# Main.net
KiCad netlist of a schematic drawn in Altium Designer
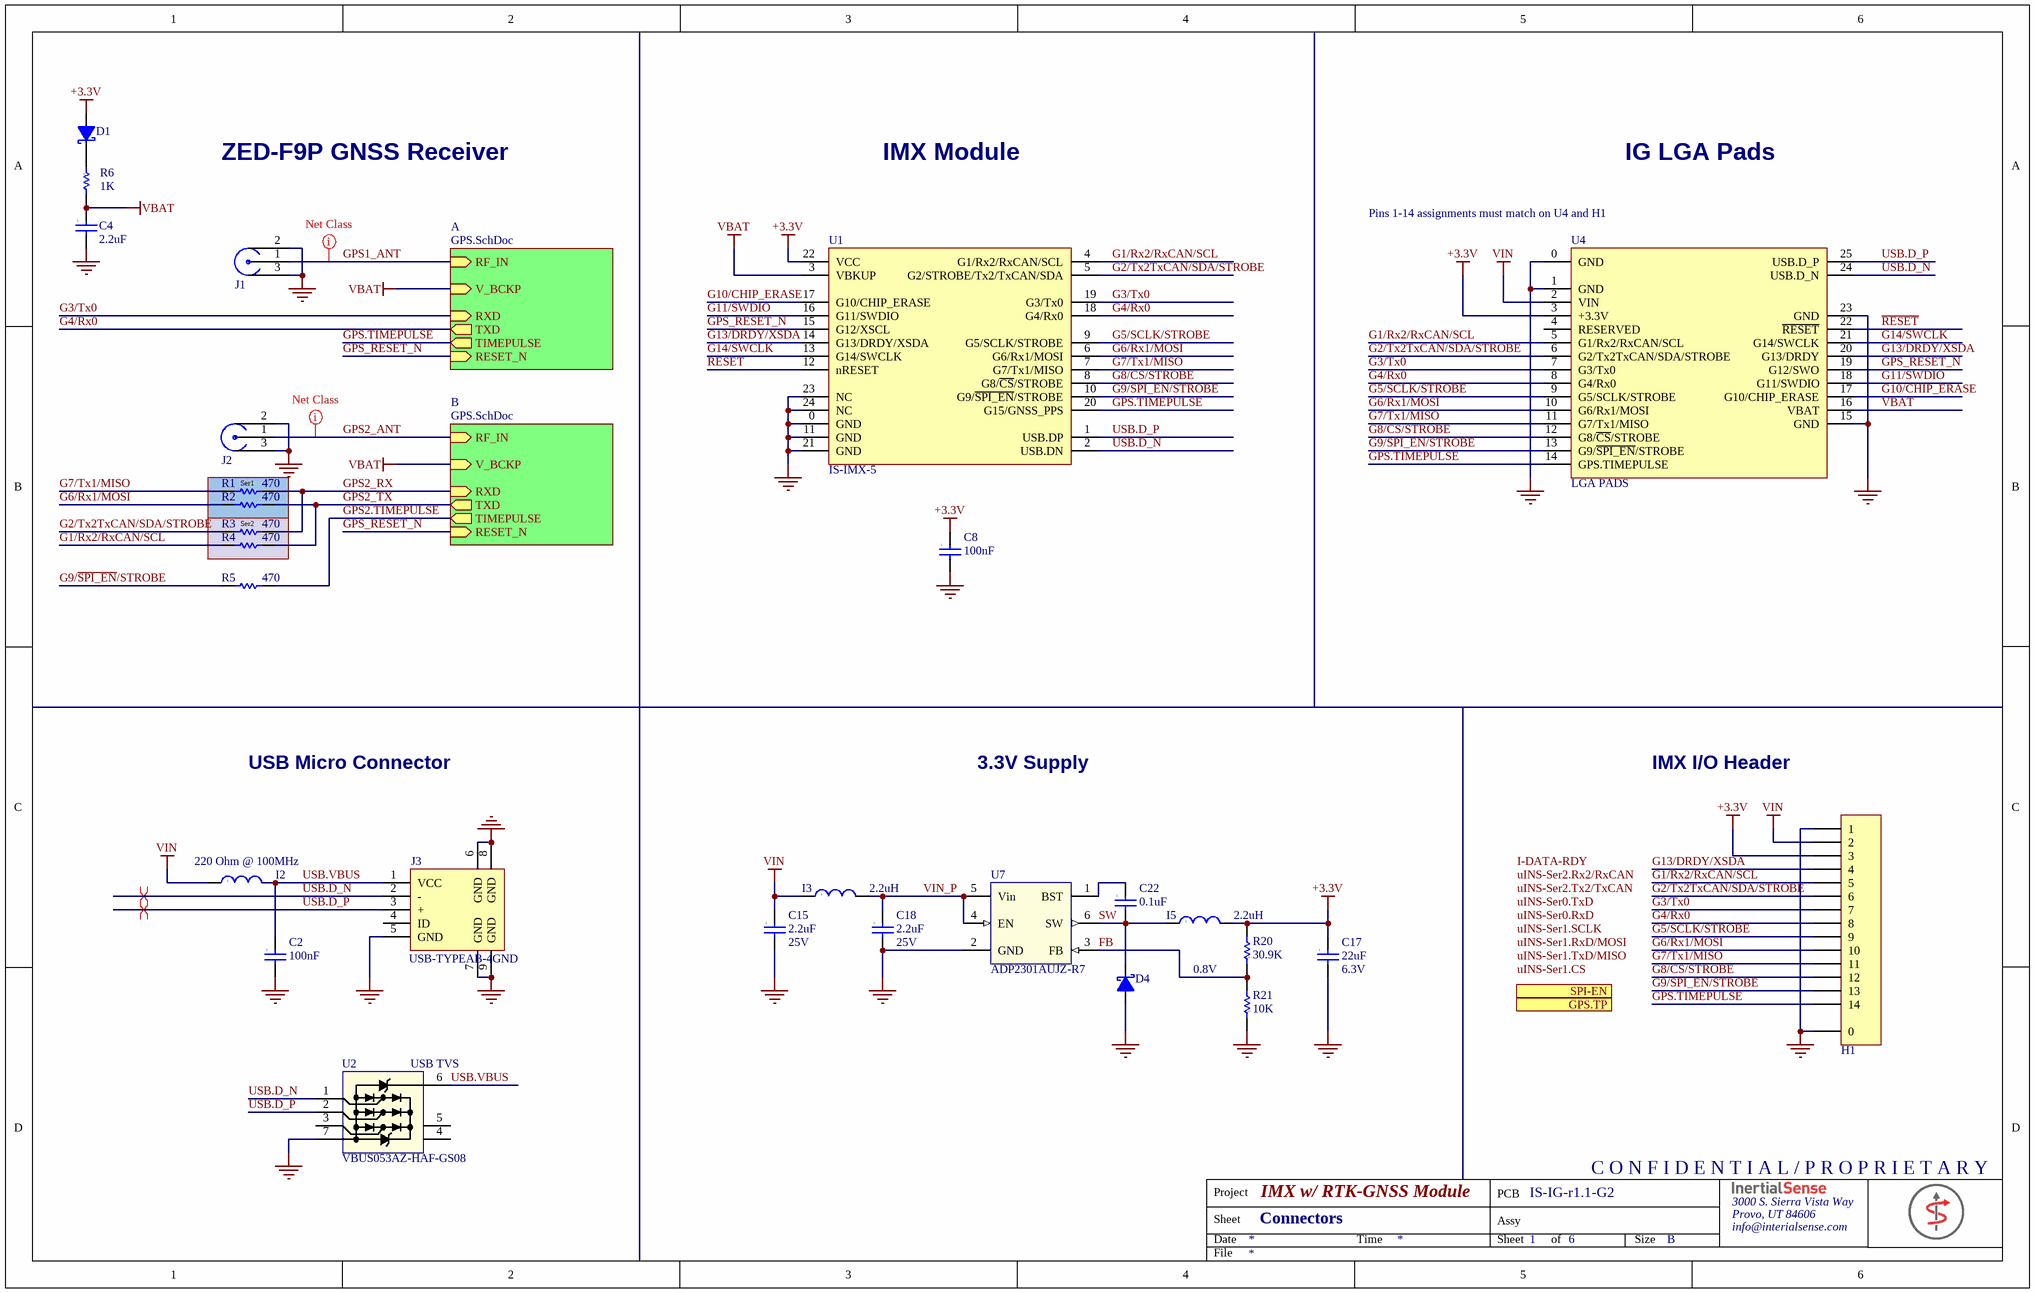
[diagram p0: Main.SchDoc]

(export (version "E")
  (design (tool "Eeschema 10.0.6"))
  (components
    (comp (ref "C2")
      (value "100nF")
      (footprint "0402")
      (description "CAP CER .10UF 50V X7R 10% 0402")
      (fields
        (field (name "MANUFACTURER") "TDK Corporation")
        (field (name "MANUFACTURER PART NUMBER") "C1005X7R1H104K")
        (field (name "PUBLISHER") "Altium Limited")
      )
      (libsource (lib "") (part "Cap_1"))
    )
    (comp (ref "C4")
      (value "2.2uF")
      (footprint "0402")
      (description "0402 2.2 uF 6.3 V ±10% Tolerance X6S Multilayer Ceramic Capacitor")
      (fields
        (field (name "MANUFACTURER") "Murata")
        (field (name "MANUFACTURER PART NUMBER") "GRM155C80J225KE95D")
        (field (name "PUBLISHER") "Altium Limited")
      )
      (libsource (lib "General") (part "Cap"))
    )
    (comp (ref "C8")
      (value "100nF")
      (footprint "0402")
      (description "CAP CER .10UF 50V X7R 10% 0402")
      (fields
        (field (name "MANUFACTURER") "TDK Corporation")
        (field (name "MANUFACTURER PART NUMBER") "C1005X7R1H104K")
        (field (name "PUBLISHER") "Altium Limited")
      )
      (libsource (lib "") (part "Cap_1"))
    )
    (comp (ref "C15")
      (value "2.2uF")
      (footprint "0603")
      (description "CAP CER 2.2UF 25V X6S 0603")
      (fields
        (field (name "MANUFACTURER") "Murata")
        (field (name "MANUFACTURER PART NUMBER") "GRT188C81E225KE13D")
        (field (name "VOLTAGE RATING") "25V")
        (field (name "PUBLISHER") "Altium Limited")
      )
      (libsource (lib "General") (part "Cap"))
    )
    (comp (ref "C17")
      (value "22uF")
      (footprint "0603")
      (description "CAP CER 22UF 6.3V X6S 0603")
      (fields
        (field (name "MANUFACTURER") "Murata")
        (field (name "MANUFACTURER PART NUMBER") "GRM188C80J226ME15D")
        (field (name "VOLTAGE RATING") "6.3V")
        (field (name "PUBLISHER") "Altium Limited")
      )
      (libsource (lib "General") (part "Cap"))
    )
    (comp (ref "C18")
      (value "2.2uF")
      (footprint "0603")
      (description "CAP CER 2.2UF 25V X6S 0603")
      (fields
        (field (name "MANUFACTURER") "Murata")
        (field (name "MANUFACTURER PART NUMBER") "GRT188C81E225KE13D")
        (field (name "VOLTAGE RATING") "25V")
        (field (name "PUBLISHER") "Altium Limited")
      )
      (libsource (lib "General") (part "Cap"))
    )
    (comp (ref "C22")
      (value "0.1uF")
      (footprint "0402")
      (description "CAP CER 0.1UF 50V X7R 0402")
      (fields
        (field (name "MANUFACTURER") "TDK")
        (field (name "MANUFACTURER PART NUMBER") "CGA2B3X7R1H104K050BB")
        (field (name "PUBLISHER") "Altium Limited")
      )
      (libsource (lib "General") (part "Cap"))
    )
    (comp (ref "D1")
      (value "Diode - Schottky")
      (footprint "D0603B")
      (description "DIODE SCHOTTKY 30V 2A 0603")
      (fields
        (field (name "MANUFACTURER") "Vishay")
        (field (name "MANUFACTURER PART NUMBER") "VSKY20301608-G4-08")
      )
      (libsource (lib "General") (part "Diode - Schottky"))
    )
    (comp (ref "D4")
      (value "Diode - Schottky")
      (footprint "D0603B")
      (description "DIODE SCHOTTKY 30V 2A 0603")
      (fields
        (field (name "MANUFACTURER") "Vishay")
        (field (name "MANUFACTURER PART NUMBER") "VSKY20301608-G4-08")
      )
      (libsource (lib "General") (part "Diode - Schottky"))
    )
    (comp (ref "H1")
      (value "Hdr - 14pin - mount")
      (footprint "SM14B-GHS-TB(LF)(SN)")
      (description "Conn Shrouded Header HDR 14 POS 1.25mm Solder ST Top Entry SMD T/R")
      (fields
        (field (name "MANUFACTURER") "JST")
        (field (name "MANUFACTURER PART NUMBER") "SM14B-GHS-TB(LF)(SN)")
      )
      (libsource (lib "Connectors") (part "Hdr - 14pin - mount"))
    )
    (comp (ref "I2")
      (value "220 Ohm @ 100MHz")
      (footprint "I0603")
      (description "FERRITE CHIP 220 OHM 2500MA 0603")
      (fields
        (field (name "MANUFACTURER") "Murata Electronics North America")
        (field (name "MANUFACTURER PART NUMBER") "BLM18SG221TN1D")
      )
      (libsource (lib "") (part "Inductor_1"))
    )
    (comp (ref "I3")
      (value "2.2uH")
      (footprint "0806")
      (description "FIXED IND 2.2UH 1.2A 110 MOHM")
      (fields
        (field (name "MANUFACTURER") "TDK")
        (field (name "MANUFACTURER PART NUMBER") "MLP2016H2R2MT0S1")
      )
      (libsource (lib "General") (part "Inductor"))
    )
    (comp (ref "I5")
      (value "2.2uH")
      (footprint "0806")
      (description "FIXED IND 2.2UH 1.2A 110 MOHM")
      (fields
        (field (name "MANUFACTURER") "TDK")
        (field (name "MANUFACTURER PART NUMBER") "MLP2016H2R2MT0S1")
      )
      (libsource (lib "General") (part "Inductor"))
    )
    (comp (ref "J1")
      (value "RF - GND x 2")
      (footprint "RF UMC SMD")
      (description "CONN UMC RCPT STR 50 OHM SMD")
      (fields
        (field (name "MANUFACTURER") "Emerson Network Power Connectivity Johnson")
        (field (name "MANUFACTURER PART NUMBER") "128-0711-201")
      )
      (libsource (lib "Connectors") (part "RF - GND x 2"))
    )
    (comp (ref "J2")
      (value "RF - GND x 2")
      (footprint "RF UMC SMD")
      (description "CONN UMC RCPT STR 50 OHM SMD")
      (fields
        (field (name "MANUFACTURER") "Emerson Network Power Connectivity Johnson")
        (field (name "MANUFACTURER PART NUMBER") "128-0711-201")
      )
      (libsource (lib "Connectors") (part "RF - GND x 2"))
    )
    (comp (ref "J3")
      (value "USB-TYPEAB-4GND")
      (footprint "USB Micro AB R/A THR")
      (description "CONN USB AB 4POS")
      (fields
        (field (name "MANUFACTURER") "Amphenol FCI")
        (field (name "MANUFACTURER PART NUMBER") "10118194-0001LF")
      )
      (libsource (lib "Connectors") (part "USB-TYPEAB-4GND"))
    )
    (comp (ref "R1")
      (value "470")
      (footprint "R0402")
      (description "RES 470 OHM 1/16W 1% 0402 SMD")
      (fields
        (field (name "MANUFACTURER") "Vishay Dale")
        (field (name "MANUFACTURER PART NUMBER") "CRCW0402470RFKED")
      )
      (libsource (lib "") (part "Res_1"))
    )
    (comp (ref "R2")
      (value "470")
      (footprint "R0402")
      (description "RES 470 OHM 1/16W 1% 0402 SMD")
      (fields
        (field (name "MANUFACTURER") "Vishay Dale")
        (field (name "MANUFACTURER PART NUMBER") "CRCW0402470RFKED")
      )
      (libsource (lib "") (part "Res_1"))
    )
    (comp (ref "R3")
      (value "470")
      (footprint "R0402")
      (description "RES 470 OHM 1/16W 1% 0402 SMD")
      (fields
        (field (name "MANUFACTURER") "Vishay Dale")
        (field (name "MANUFACTURER PART NUMBER") "CRCW0402470RFKED")
      )
      (libsource (lib "") (part "Res_1"))
    )
    (comp (ref "R4")
      (value "470")
      (footprint "R0402")
      (description "RES 470 OHM 1/16W 1% 0402 SMD")
      (fields
        (field (name "MANUFACTURER") "Vishay Dale")
        (field (name "MANUFACTURER PART NUMBER") "CRCW0402470RFKED")
      )
      (libsource (lib "") (part "Res_1"))
    )
    (comp (ref "R5")
      (value "470")
      (footprint "R0402")
      (description "RES 470 OHM 1/16W 1% 0402 SMD")
      (fields
        (field (name "MANUFACTURER") "Vishay Dale")
        (field (name "MANUFACTURER PART NUMBER") "CRCW0402470RFKED")
      )
      (libsource (lib "") (part "Res_1"))
    )
    (comp (ref "R6")
      (value "1K")
      (footprint "R0402")
      (description "1 kOhms ±1% 0.063W, 1/16W Chip Resistor 0402 (1005 Metric) Moisture Resistant Thick Film")
      (fields
        (field (name "MANUFACTURER") "Yageo")
        (field (name "MANUFACTURER PART NUMBER") "RC0402FR-071KL")
      )
      (libsource (lib "") (part "Res_2"))
    )
    (comp (ref "R20")
      (value "30.9K")
      (footprint "R0402")
      (description "RES TF 30.9K OHM 1% 1/16W 0402")
      (fields
        (field (name "MANUFACTURER") "Stackpole Electronics Inc")
        (field (name "MANUFACTURER PART NUMBER") "RMCF0402FT30K9")
      )
      (libsource (lib "General") (part "Res"))
    )
    (comp (ref "R21")
      (value "10K")
      (footprint "R0402")
      (description "RES 10.0K OHM 1/16W 1% 0402 SMD")
      (fields
        (field (name "MANUFACTURER") "Yageo")
        (field (name "MANUFACTURER PART NUMBER") "RC0402FR-0710KL")
      )
      (libsource (lib "General") (part "Res"))
    )
    (comp (ref "U1")
      (value "IMX")
      (footprint "IS-IMX-5.0")
      (description "Inertial Sense IMX")
      (fields
        (field (name "MANUFACTURER") "Inertial Sense")
        (field (name "MANUFACTURER PART NUMBER") "IS-IMX-5")
      )
      (libsource (lib "IS-IMX-5") (part "IS-IMX-5.0"))
    )
    (comp (ref "U2")
      (value "VBUS053")
      (footprint "QFN50P160X160X60-6N")
      (description "ESD SUPPRESS 5.5V 36W 3-Line USB")
      (fields
        (field (name "MANUFACTURER") "Vishay Semiconductors")
        (field (name "MANUFACTURER PART NUMBER") "VBUS053AZ-HAF-GS08")
      )
      (libsource (lib "ICs") (part "VBUS053"))
    )
    (comp (ref "U4")
      (value "LGA PADS")
      (footprint "IG-1.1-G1_LGA")
      (description "IMX multi-frequency RTK-GNSS Module")
      (libsource (lib "Sensors") (part "IG_1.1_LGA"))
    )
    (comp (ref "U7")
      (value "ADP2301")
      (footprint "MO-178-AB")
      (description "IC BUCK ADJ 1.2A 6TSOT")
      (fields
        (field (name "MANUFACTURER") "Analog Devices Inc")
        (field (name "MANUFACTURER PART NUMBER") "ADP2301AUJZ-R7")
      )
      (libsource (lib "ICs") (part "ADP2301"))
    )
  )
  (nets
    (net (code "1") (name "+3.3V") (class "Default")
      (node (ref "C17") (pin "1") (pinfunction "1_1") (pintype "passive"))
      (node (ref "C8") (pin "1") (pinfunction "1_1") (pintype "passive"))
      (node (ref "D1") (pin "A") (pinfunction "A_A") (pintype "passive"))
      (node (ref "H1") (pin "3") (pinfunction "3_3") (pintype "passive"))
      (node (ref "I5") (pin "2") (pinfunction "2_2") (pintype "passive"))
      (node (ref "R20") (pin "2") (pinfunction "2_2") (pintype "passive"))
      (node (ref "U1") (pin "22") (pinfunction "VCC_22") (pintype "power_in"))
      (node (ref "U4") (pin "3") (pinfunction "+3.3V_3") (pintype "passive"))
    )
    (net (code "2") (name "/FB") (class "Default")
      (node (ref "R20") (pin "1") (pinfunction "1_1") (pintype "passive"))
      (node (ref "R21") (pin "2") (pinfunction "2_2") (pintype "passive"))
      (node (ref "U7") (pin "3") (pinfunction "FB_3") (pintype "input"))
    )
    (net (code "3") (name "/G1{slash}Rx2{slash}RxCAN{slash}SCL") (class "Default")
      (node (ref "H1") (pin "5") (pinfunction "5_5") (pintype "passive"))
      (node (ref "R4") (pin "1") (pinfunction "1_1") (pintype "passive"))
      (node (ref "U1") (pin "4") (pinfunction "G1/Rx2/RxCAN/SCL_4") (pintype "passive"))
      (node (ref "U4") (pin "5") (pinfunction "G1/Rx2/RxCAN/SCL_5") (pintype "passive"))
    )
    (net (code "4") (name "/G2{slash}Tx2TxCAN{slash}SDA{slash}STROBE") (class "Default")
      (node (ref "H1") (pin "6") (pinfunction "6_6") (pintype "passive"))
      (node (ref "R3") (pin "1") (pinfunction "1_1") (pintype "passive"))
      (node (ref "U1") (pin "5") (pinfunction "G2/STROBE/Tx2/TxCAN/SDA_5") (pintype "passive"))
      (node (ref "U4") (pin "6") (pinfunction "G2/Tx2TxCAN/SDA/STROBE_6") (pintype "passive"))
    )
    (net (code "5") (name "/G3{slash}Tx0") (class "Default")
      (node (ref "H1") (pin "7") (pinfunction "7_7") (pintype "passive"))
      (node (ref "U1") (pin "19") (pinfunction "G3/Tx0_19") (pintype "passive"))
      (node (ref "U4") (pin "7") (pinfunction "G3/Tx0_7") (pintype "passive"))
    )
    (net (code "6") (name "/G4{slash}Rx0") (class "Default")
      (node (ref "H1") (pin "8") (pinfunction "8_8") (pintype "passive"))
      (node (ref "U1") (pin "18") (pinfunction "G4/Rx0_18") (pintype "passive"))
      (node (ref "U4") (pin "8") (pinfunction "G4/Rx0_8") (pintype "passive"))
    )
    (net (code "7") (name "/G5{slash}SCLK{slash}STROBE") (class "Default")
      (node (ref "H1") (pin "9") (pinfunction "9_9") (pintype "passive"))
      (node (ref "U1") (pin "9") (pinfunction "G5/SCLK/STROBE_9") (pintype "passive"))
      (node (ref "U4") (pin "9") (pinfunction "G5/SCLK/STROBE_9") (pintype "passive"))
    )
    (net (code "8") (name "/G6{slash}Rx1{slash}MOSI") (class "Default")
      (node (ref "H1") (pin "10") (pinfunction "10_10") (pintype "passive"))
      (node (ref "R2") (pin "1") (pinfunction "1_1") (pintype "passive"))
      (node (ref "U1") (pin "6") (pinfunction "G6/Rx1/MOSI_6") (pintype "passive"))
      (node (ref "U4") (pin "10") (pinfunction "G6/Rx1/MOSI_10") (pintype "passive"))
    )
    (net (code "9") (name "/G7{slash}Tx1{slash}MISO") (class "Default")
      (node (ref "H1") (pin "11") (pinfunction "11_11") (pintype "passive"))
      (node (ref "R1") (pin "1") (pinfunction "1_1") (pintype "passive"))
      (node (ref "U1") (pin "7") (pinfunction "G7/Tx1/MISO_7") (pintype "passive"))
      (node (ref "U4") (pin "11") (pinfunction "G7/Tx1/MISO_11") (pintype "passive"))
    )
    (net (code "10") (name "/G8{slash}~{CS}{slash}STROBE") (class "Default")
      (node (ref "H1") (pin "12") (pinfunction "12_12") (pintype "passive"))
      (node (ref "U1") (pin "8") (pinfunction "G8/~{CS}/STROBE_8") (pintype "passive"))
      (node (ref "U4") (pin "12") (pinfunction "G8/~{CS}/STROBE_12") (pintype "passive"))
    )
    (net (code "11") (name "/G9{slash}~{SPI_EN}{slash}STROBE") (class "Default")
      (node (ref "H1") (pin "13") (pinfunction "13_13") (pintype "passive"))
      (node (ref "R5") (pin "1") (pinfunction "1_1") (pintype "passive"))
      (node (ref "U1") (pin "10") (pinfunction "G9/~{SPI_EN}/STROBE_10") (pintype "passive"))
      (node (ref "U4") (pin "13") (pinfunction "G9/~{SPI_EN}/STROBE_13") (pintype "passive"))
    )
    (net (code "12") (name "/G10{slash}CHIP_ERASE") (class "Default")
      (node (ref "U1") (pin "17") (pinfunction "G10/CHIP_ERASE_17") (pintype "passive"))
      (node (ref "U4") (pin "17") (pinfunction "G10/CHIP_ERASE_17") (pintype "passive"))
    )
    (net (code "13") (name "/G11{slash}SWDIO") (class "Default")
      (node (ref "U1") (pin "16") (pinfunction "G11/SWDIO_16") (pintype "passive"))
      (node (ref "U4") (pin "18") (pinfunction "G11/SWDIO_18") (pintype "passive"))
    )
    (net (code "14") (name "/G13{slash}DRDY{slash}XSDA") (class "Default")
      (node (ref "H1") (pin "4") (pinfunction "4_4") (pintype "passive"))
      (node (ref "U1") (pin "14") (pinfunction "G13/DRDY/XSDA_14") (pintype "passive"))
      (node (ref "U4") (pin "20") (pinfunction "G13/DRDY_20") (pintype "passive"))
    )
    (net (code "15") (name "/G14{slash}SWCLK") (class "Default")
      (node (ref "U1") (pin "13") (pinfunction "G14/SWCLK_13") (pintype "passive"))
      (node (ref "U4") (pin "21") (pinfunction "G14/SWCLK_21") (pintype "passive"))
    )
    (net (code "16") (name "/GPS.TIMEPULSE") (class "Default")
      (node (ref "H1") (pin "14") (pinfunction "14_14") (pintype "passive"))
      (node (ref "U1") (pin "20") (pinfunction "G15/GNSS_PPS_20") (pintype "passive"))
      (node (ref "U4") (pin "14") (pinfunction "GPS.TIMEPULSE_14") (pintype "passive"))
    )
    (net (code "18") (name "/GPS1_ANT") (class "Default")
      (node (ref "J1") (pin "1") (pinfunction "1_1") (pintype "passive"))
    )
    (net (code "19") (name "/GPS2.TIMEPULSE") (class "Default")
      (node (ref "R5") (pin "2") (pinfunction "2_2") (pintype "passive"))
    )
    (net (code "20") (name "/GPS2_ANT") (class "Default")
      (node (ref "J2") (pin "1") (pinfunction "1_1") (pintype "passive"))
    )
    (net (code "21") (name "/GPS2_RX") (class "Default")
      (node (ref "R1") (pin "2") (pinfunction "2_2") (pintype "passive"))
      (node (ref "R3") (pin "2") (pinfunction "2_2") (pintype "passive"))
    )
    (net (code "22") (name "/GPS2_TX") (class "Default")
      (node (ref "R2") (pin "2") (pinfunction "2_2") (pintype "passive"))
      (node (ref "R4") (pin "2") (pinfunction "2_2") (pintype "passive"))
    )
    (net (code "23") (name "/GPS_RESET_N") (class "Default")
      (node (ref "U1") (pin "15") (pinfunction "G12/XSCL_15") (pintype "passive"))
      (node (ref "U4") (pin "19") (pinfunction "G12/SWO_19") (pintype "passive"))
    )
    (net (code "25") (name "/RESET") (class "Default")
      (node (ref "U1") (pin "12") (pinfunction "nRESET_12") (pintype "passive"))
      (node (ref "U4") (pin "22") (pinfunction "~{RESET}_22") (pintype "passive"))
    )
    (net (code "27") (name "/SW") (class "Default")
      (node (ref "C22") (pin "2") (pinfunction "2_2") (pintype "passive"))
      (node (ref "D4") (pin "C") (pinfunction "C_C") (pintype "passive"))
      (node (ref "I5") (pin "1") (pinfunction "1_1") (pintype "passive"))
      (node (ref "U7") (pin "6") (pinfunction "SW_6") (pintype "output"))
    )
    (net (code "28") (name "/USB.D_N") (class "Default")
      (node (ref "J3") (pin "2") (pinfunction "-_2") (pintype "passive"))
      (node (ref "U1") (pin "2") (pinfunction "USB.DN_2") (pintype "passive"))
      (node (ref "U2") (pin "1") (pintype "passive"))
      (node (ref "U4") (pin "24") (pinfunction "USB.D_N_24") (pintype "passive"))
    )
    (net (code "29") (name "/USB.D_P") (class "Default")
      (node (ref "J3") (pin "3") (pinfunction "+_3") (pintype "passive"))
      (node (ref "U1") (pin "1") (pinfunction "USB.DP_1") (pintype "passive"))
      (node (ref "U2") (pin "2") (pintype "passive"))
      (node (ref "U4") (pin "25") (pinfunction "USB.D_P_25") (pintype "passive"))
    )
    (net (code "30") (name "/USB.VBUS") (class "Default")
      (node (ref "C2") (pin "1") (pinfunction "1_1") (pintype "passive"))
      (node (ref "I2") (pin "2") (pinfunction "2_2") (pintype "passive"))
      (node (ref "J3") (pin "1") (pinfunction "VCC_1") (pintype "passive"))
      (node (ref "U2") (pin "6") (pintype "passive"))
    )
    (net (code "31") (name "/VIN_P") (class "Default")
      (node (ref "C18") (pin "1") (pinfunction "1_1") (pintype "passive"))
      (node (ref "I3") (pin "2") (pinfunction "2_2") (pintype "passive"))
      (node (ref "U7") (pin "4") (pinfunction "EN_4") (pintype "input"))
      (node (ref "U7") (pin "5") (pinfunction "Vin_5") (pintype "power_in"))
    )
    (net (code "40") (name "GND") (class "Default")
      (node (ref "C15") (pin "2") (pinfunction "2_2") (pintype "passive"))
      (node (ref "C17") (pin "2") (pinfunction "2_2") (pintype "passive"))
      (node (ref "C18") (pin "2") (pinfunction "2_2") (pintype "passive"))
      (node (ref "C2") (pin "2") (pinfunction "2_2") (pintype "passive"))
      (node (ref "C4") (pin "2") (pinfunction "2_2") (pintype "passive"))
      (node (ref "C8") (pin "2") (pinfunction "2_2") (pintype "passive"))
      (node (ref "D4") (pin "A") (pinfunction "A_A") (pintype "passive"))
      (node (ref "H1") (pin "0") (pinfunction "0_0") (pintype "passive"))
      (node (ref "H1") (pin "1") (pinfunction "1_1") (pintype "passive"))
      (node (ref "J1") (pin "2") (pinfunction "2_2") (pintype "passive"))
      (node (ref "J1") (pin "3") (pinfunction "3_3") (pintype "passive"))
      (node (ref "J2") (pin "2") (pinfunction "2_2") (pintype "passive"))
      (node (ref "J2") (pin "3") (pinfunction "3_3") (pintype "passive"))
      (node (ref "J3") (pin "5") (pinfunction "GND_5") (pintype "passive"))
      (node (ref "J3") (pin "6") (pinfunction "GND_6") (pintype "passive"))
      (node (ref "J3") (pin "7") (pinfunction "GND_7") (pintype "passive"))
      (node (ref "J3") (pin "8") (pinfunction "GND_8") (pintype "passive"))
      (node (ref "J3") (pin "9") (pinfunction "GND_9") (pintype "passive"))
      (node (ref "R21") (pin "1") (pinfunction "1_1") (pintype "passive"))
      (node (ref "U1") (pin "0") (pinfunction "GND_0") (pintype "power_in"))
      (node (ref "U1") (pin "11") (pinfunction "GND_11") (pintype "power_in"))
      (node (ref "U1") (pin "21") (pinfunction "GND_21") (pintype "power_in"))
      (node (ref "U1") (pin "23") (pinfunction "NC_23") (pintype "power_in"))
      (node (ref "U1") (pin "24") (pinfunction "NC_24") (pintype "power_in"))
      (node (ref "U2") (pin "7") (pintype "passive"))
      (node (ref "U4") (pin "0") (pinfunction "GND_0") (pintype "passive"))
      (node (ref "U4") (pin "1") (pinfunction "GND_1") (pintype "passive"))
      (node (ref "U4") (pin "15") (pinfunction "GND_15") (pintype "passive"))
      (node (ref "U4") (pin "23") (pinfunction "GND_23") (pintype "passive"))
      (node (ref "U7") (pin "2") (pinfunction "GND_2") (pintype "power_in"))
    )
    (net (code "41") (name "Net-(D1-PadC)") (class "Default")
      (node (ref "D1") (pin "C") (pinfunction "C_C") (pintype "passive"))
      (node (ref "R6") (pin "1") (pinfunction "1_1") (pintype "passive"))
    )
    (net (code "42") (name "Net-(U7-BST)") (class "Default")
      (node (ref "C22") (pin "1") (pinfunction "1_1") (pintype "passive"))
      (node (ref "U7") (pin "1") (pinfunction "BST_1") (pintype "passive"))
    )
    (net (code "43") (name "VBAT") (class "Default")
      (node (ref "C4") (pin "1") (pinfunction "1_1") (pintype "passive"))
      (node (ref "R6") (pin "2") (pinfunction "2_2") (pintype "passive"))
      (node (ref "U1") (pin "3") (pinfunction "VBKUP_3") (pintype "passive"))
      (node (ref "U4") (pin "16") (pinfunction "VBAT_16") (pintype "passive"))
    )
    (net (code "44") (name "VIN") (class "Default")
      (node (ref "C15") (pin "1") (pinfunction "1_1") (pintype "passive"))
      (node (ref "H1") (pin "2") (pinfunction "2_2") (pintype "passive"))
      (node (ref "I2") (pin "1") (pinfunction "1_1") (pintype "passive"))
      (node (ref "I3") (pin "1") (pinfunction "1_1") (pintype "passive"))
      (node (ref "U4") (pin "2") (pinfunction "VIN_2") (pintype "passive"))
    )
    (net (code "45") (name "unconnected-(J3-ID-Pad4)") (class "Default")
      (node (ref "J3") (pin "4") (pinfunction "ID_4") (pintype "passive"))
    )
    (net (code "46") (name "unconnected-(U2-Pad3)") (class "Default")
      (node (ref "U2") (pin "3") (pintype "passive"))
    )
    (net (code "47") (name "unconnected-(U2-nc-Pad4)") (class "Default")
      (node (ref "U2") (pin "4") (pinfunction "nc_4") (pintype "passive"))
    )
    (net (code "48") (name "unconnected-(U2-nc-Pad5)") (class "Default")
      (node (ref "U2") (pin "5") (pinfunction "nc_5") (pintype "passive"))
    )
    (net (code "49") (name "unconnected-(U4-RESERVED-Pad4)") (class "Default")
      (node (ref "U4") (pin "4") (pinfunction "RESERVED_4") (pintype "passive"))
    )
  )
)
